# RF_Connectors.net
KiCad netlist of a schematic drawn in Altium Designer
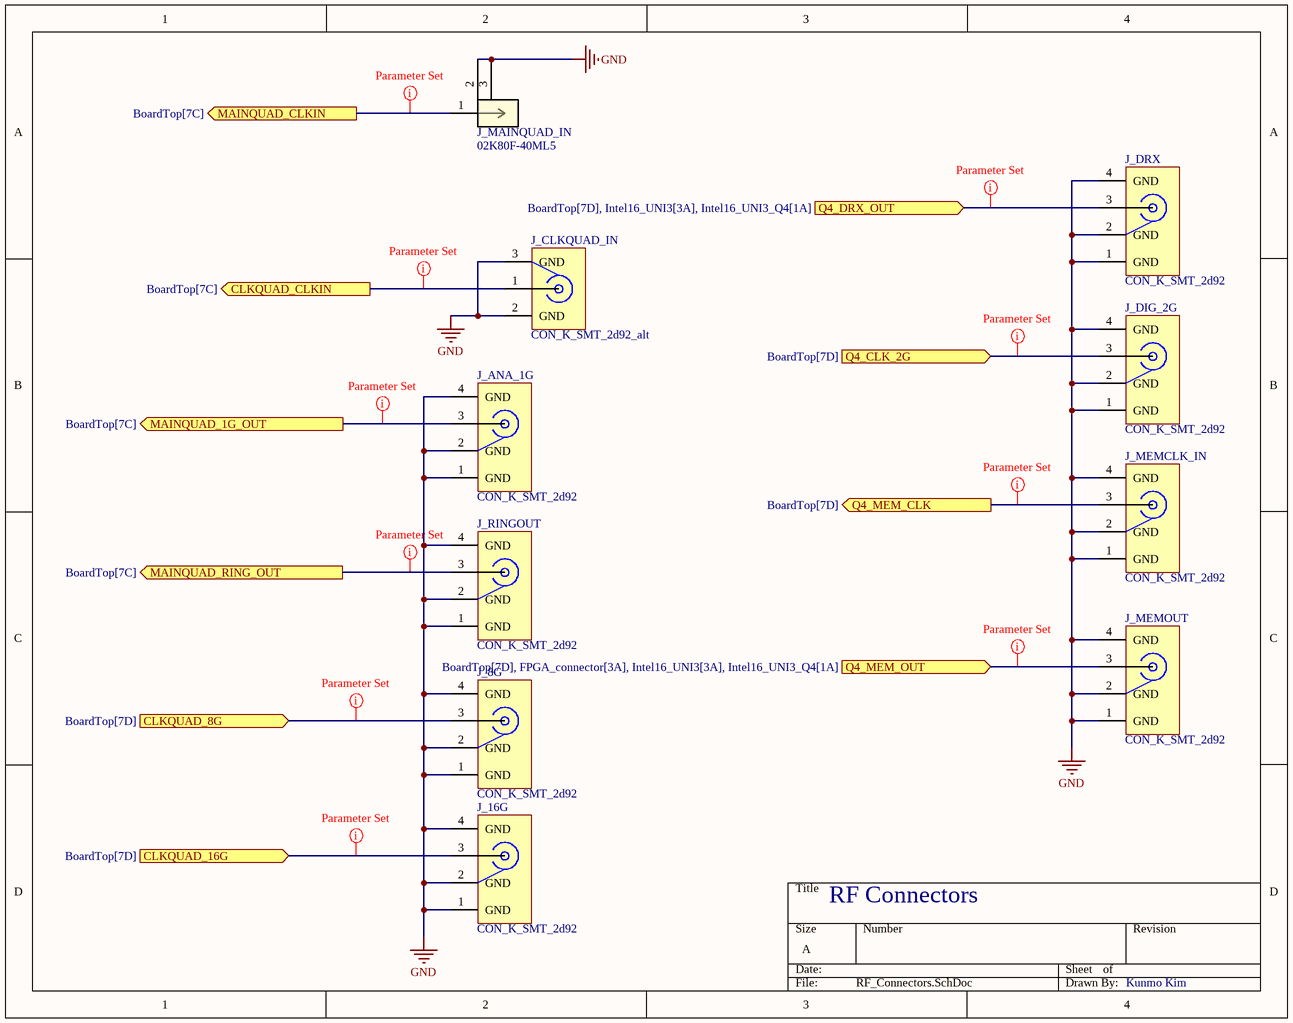
[diagram p0: RF_Connectors.SchDoc]

(export (version "E")
  (design (tool "Eeschema 10.0.6"))
  (components
    (comp (ref "J_8G")
      (value "CON_K_SMT_2d92")
      (footprint "CON_K_SMT_2D92_3")
      (description "Con RF K")
      (libsource (lib "BWRC") (part "CON_K_SMT_2d92"))
    )
    (comp (ref "J_16G")
      (value "CON_K_SMT_2d92")
      (footprint "CON_K_SMT_2D92_3")
      (description "Con RF K")
      (libsource (lib "BWRC") (part "CON_K_SMT_2d92"))
    )
    (comp (ref "J_ANA_1G")
      (value "CON_K_SMT_2d92")
      (footprint "CON_K_SMT_2D92_3")
      (description "Con RF K")
      (libsource (lib "BWRC") (part "CON_K_SMT_2d92"))
    )
    (comp (ref "J_CLKQUAD_IN")
      (value "CON_K_SMT_2d92_alt")
      (footprint "CON-001-SMA-ST - duplicate")
      (description "Con RF K")
      (libsource (lib "BWRC") (part "CON_K_SMT_2d92_alt"))
    )
    (comp (ref "J_DIG_2G")
      (value "CON_K_SMT_2d92")
      (footprint "CON_K_SMT_2D92_3")
      (description "Con RF K")
      (libsource (lib "BWRC") (part "CON_K_SMT_2d92"))
    )
    (comp (ref "J_DRX")
      (value "CON_K_SMT_2d92")
      (footprint "CON_K_SMT_2D92_3")
      (description "Con RF K")
      (libsource (lib "BWRC") (part "CON_K_SMT_2d92"))
    )
    (comp (ref "J_MAINQUAD_IN")
      (value "02K80F-40ML5")
      (footprint "CONN_02K80F-40ML5_RBG")
      (description "No Description Available")
      (libsource (lib "02K80F-40ML5_Ver2") (part "02K80F-40ML5"))
    )
    (comp (ref "J_MEMCLK_IN")
      (value "CON_K_SMT_2d92")
      (footprint "CON_K_SMT_2D92_3")
      (description "Con RF K")
      (libsource (lib "BWRC") (part "CON_K_SMT_2d92"))
    )
    (comp (ref "J_MEMOUT")
      (value "CON_K_SMT_2d92")
      (footprint "CON_K_SMT_2D92_3")
      (description "Con RF K")
      (libsource (lib "BWRC") (part "CON_K_SMT_2d92"))
    )
    (comp (ref "J_RINGOUT")
      (value "CON_K_SMT_2d92")
      (footprint "CON_K_SMT_2D92_3")
      (description "Con RF K")
      (libsource (lib "BWRC") (part "CON_K_SMT_2d92"))
    )
  )
  (nets
    (net (code "1") (name "/CLKQUAD_8G") (class "Default")
      (node (ref "J_8G") (pin "3") (pinfunction "1_3") (pintype "passive"))
    )
    (net (code "2") (name "/CLKQUAD_16G") (class "Default")
      (node (ref "J_16G") (pin "3") (pinfunction "1_3") (pintype "passive"))
    )
    (net (code "3") (name "/CLKQUAD_CLKIN") (class "Default")
      (node (ref "J_CLKQUAD_IN") (pin "1") (pinfunction "1_1") (pintype "passive"))
    )
    (net (code "4") (name "/MAINQUAD_1G_OUT") (class "Default")
      (node (ref "J_ANA_1G") (pin "3") (pinfunction "1_3") (pintype "passive"))
    )
    (net (code "5") (name "/MAINQUAD_CLKIN") (class "Default")
      (node (ref "J_MAINQUAD_IN") (pin "1") (pinfunction "1_1") (pintype "passive"))
    )
    (net (code "6") (name "/MAINQUAD_RING_OUT") (class "Default")
      (node (ref "J_RINGOUT") (pin "3") (pinfunction "1_3") (pintype "passive"))
    )
    (net (code "7") (name "/Q4_CLK_2G") (class "Default")
      (node (ref "J_DIG_2G") (pin "3") (pinfunction "1_3") (pintype "passive"))
    )
    (net (code "8") (name "/Q4_DRX_OUT") (class "Default")
      (node (ref "J_DRX") (pin "3") (pinfunction "1_3") (pintype "passive"))
    )
    (net (code "9") (name "/Q4_MEM_CLK") (class "Default")
      (node (ref "J_MEMCLK_IN") (pin "3") (pinfunction "1_3") (pintype "passive"))
    )
    (net (code "10") (name "/Q4_MEM_OUT") (class "Default")
      (node (ref "J_MEMOUT") (pin "3") (pinfunction "1_3") (pintype "passive"))
    )
    (net (code "11") (name "GND") (class "Default")
      (node (ref "J_16G") (pin "1") (pinfunction "GND_1") (pintype "passive"))
      (node (ref "J_16G") (pin "2") (pinfunction "GND_2") (pintype "passive"))
      (node (ref "J_16G") (pin "4") (pinfunction "GND_4") (pintype "passive"))
      (node (ref "J_8G") (pin "1") (pinfunction "GND_1") (pintype "passive"))
      (node (ref "J_8G") (pin "2") (pinfunction "GND_2") (pintype "passive"))
      (node (ref "J_8G") (pin "4") (pinfunction "GND_4") (pintype "passive"))
      (node (ref "J_ANA_1G") (pin "1") (pinfunction "GND_1") (pintype "passive"))
      (node (ref "J_ANA_1G") (pin "2") (pinfunction "GND_2") (pintype "passive"))
      (node (ref "J_ANA_1G") (pin "4") (pinfunction "GND_4") (pintype "passive"))
      (node (ref "J_CLKQUAD_IN") (pin "2") (pinfunction "GND_2") (pintype "passive"))
      (node (ref "J_CLKQUAD_IN") (pin "3") (pinfunction "GND_3") (pintype "passive"))
      (node (ref "J_DIG_2G") (pin "1") (pinfunction "GND_1") (pintype "passive"))
      (node (ref "J_DIG_2G") (pin "2") (pinfunction "GND_2") (pintype "passive"))
      (node (ref "J_DIG_2G") (pin "4") (pinfunction "GND_4") (pintype "passive"))
      (node (ref "J_DRX") (pin "1") (pinfunction "GND_1") (pintype "passive"))
      (node (ref "J_DRX") (pin "2") (pinfunction "GND_2") (pintype "passive"))
      (node (ref "J_DRX") (pin "4") (pinfunction "GND_4") (pintype "passive"))
      (node (ref "J_MAINQUAD_IN") (pin "2") (pinfunction "2_2") (pintype "passive"))
      (node (ref "J_MAINQUAD_IN") (pin "3") (pinfunction "3_3") (pintype "passive"))
      (node (ref "J_MEMCLK_IN") (pin "1") (pinfunction "GND_1") (pintype "passive"))
      (node (ref "J_MEMCLK_IN") (pin "2") (pinfunction "GND_2") (pintype "passive"))
      (node (ref "J_MEMCLK_IN") (pin "4") (pinfunction "GND_4") (pintype "passive"))
      (node (ref "J_MEMOUT") (pin "1") (pinfunction "GND_1") (pintype "passive"))
      (node (ref "J_MEMOUT") (pin "2") (pinfunction "GND_2") (pintype "passive"))
      (node (ref "J_MEMOUT") (pin "4") (pinfunction "GND_4") (pintype "passive"))
      (node (ref "J_RINGOUT") (pin "1") (pinfunction "GND_1") (pintype "passive"))
      (node (ref "J_RINGOUT") (pin "2") (pinfunction "GND_2") (pintype "passive"))
      (node (ref "J_RINGOUT") (pin "4") (pinfunction "GND_4") (pintype "passive"))
    )
  )
)
